# zeroport.net
KiCad netlist of a schematic drawn in EAGLE
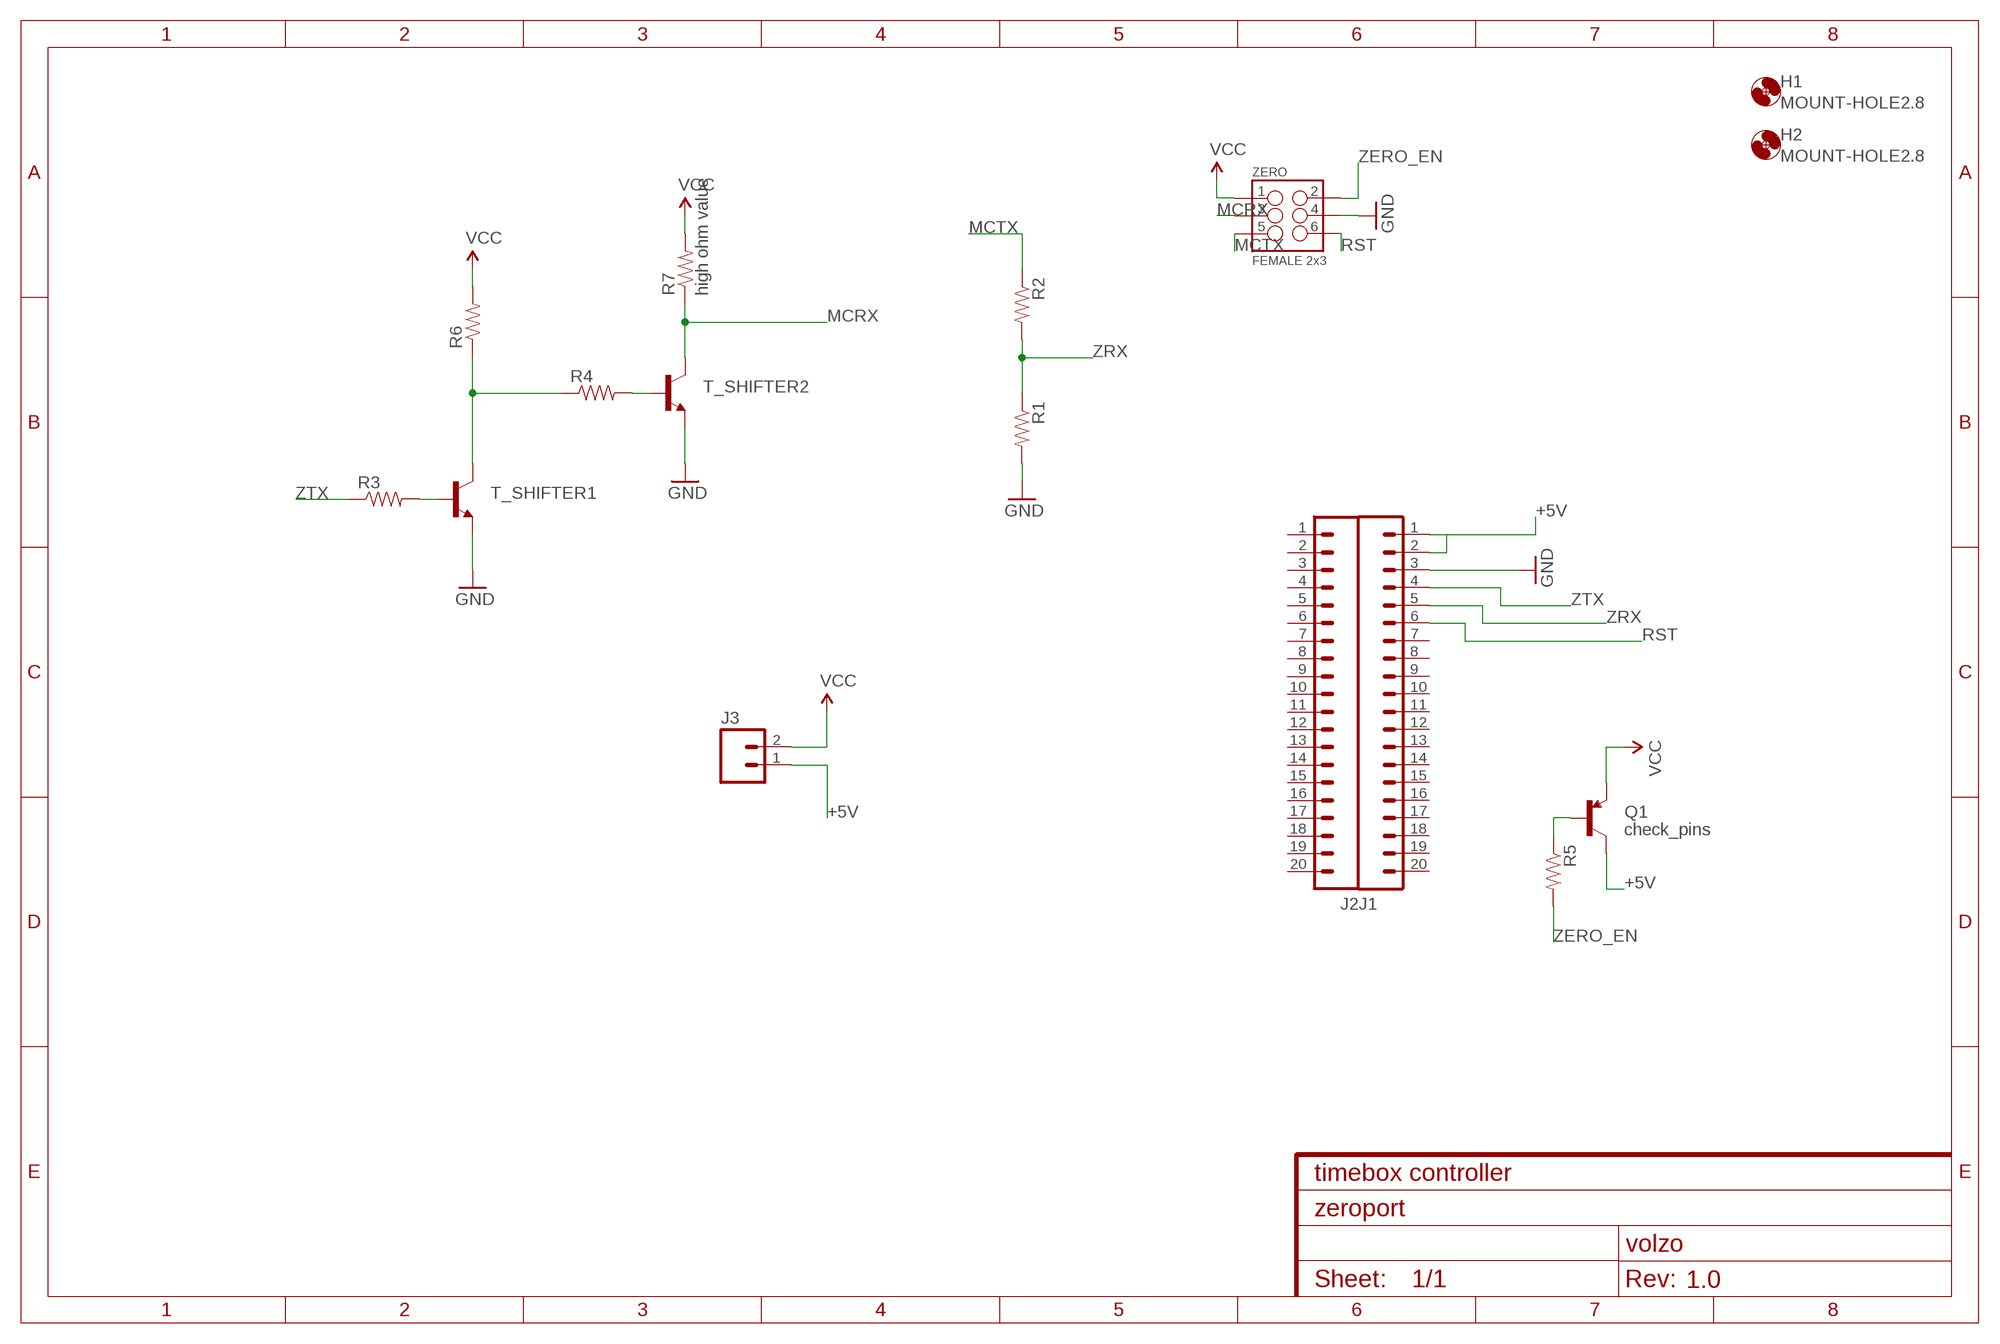
[diagram p0: schematic, sheet 1]

(export (version "E")
  (design (tool "Eeschema 10.0.6"))
  (components
    (comp (ref "H1")
      (value "MOUNT-HOLE2.8")
      (footprint "eagle-import:2,8")
      (libsource (lib "eagle-import") (part "MOUNT-HOLE2.8"))
    )
    (comp (ref "H2")
      (value "MOUNT-HOLE2.8")
      (footprint "eagle-import:2,8")
      (libsource (lib "eagle-import") (part "MOUNT-HOLE2.8"))
    )
    (comp (ref "J1")
      (value "M20LOCK")
      (footprint "eagle-import:1X20_LOCK")
      (libsource (lib "eagle-import") (part "M20LOCK"))
    )
    (comp (ref "J2")
      (value "M20LOCK")
      (footprint "eagle-import:1X20_LOCK")
      (libsource (lib "eagle-import") (part "M20LOCK"))
    )
    (comp (ref "J3")
      (value "M02LOCK")
      (footprint "eagle-import:1X02_LOCK")
      (libsource (lib "eagle-import") (part "M02LOCK"))
    )
    (comp (ref "Q1")
      (value "check_pins")
      (footprint "eagle-import:TO-92")
      (libsource (lib "eagle-import") (part "TRANSISTOR_PNPTO92"))
    )
    (comp (ref "R1")
      (value "RESISTORPTH-1/4W")
      (footprint "eagle-import:AXIAL-0.4")
      (libsource (lib "eagle-import") (part "RESISTORPTH-1/4W"))
    )
    (comp (ref "R2")
      (value "RESISTORPTH-1/4W")
      (footprint "eagle-import:AXIAL-0.4")
      (libsource (lib "eagle-import") (part "RESISTORPTH-1/4W"))
    )
    (comp (ref "R3")
      (value "RESISTORPTH-1/4W")
      (footprint "eagle-import:AXIAL-0.4")
      (libsource (lib "eagle-import") (part "RESISTORPTH-1/4W"))
    )
    (comp (ref "R4")
      (value "RESISTORPTH-1/4W")
      (footprint "eagle-import:AXIAL-0.4")
      (libsource (lib "eagle-import") (part "RESISTORPTH-1/4W"))
    )
    (comp (ref "R5")
      (value "RESISTORPTH-1/4W")
      (footprint "eagle-import:AXIAL-0.4")
      (libsource (lib "eagle-import") (part "RESISTORPTH-1/4W"))
    )
    (comp (ref "R6")
      (value "RESISTORPTH-1/4W")
      (footprint "eagle-import:AXIAL-0.4")
      (libsource (lib "eagle-import") (part "RESISTORPTH-1/4W"))
    )
    (comp (ref "R7")
      (value "high ohm value")
      (footprint "eagle-import:AXIAL-0.4")
      (libsource (lib "eagle-import") (part "RESISTORPTH-1/4W"))
    )
    (comp (ref "T_SHIFTER1")
      (value "TRANSISTOR_NPN2N3904")
      (footprint "eagle-import:TO-92")
      (libsource (lib "eagle-import") (part "TRANSISTOR_NPN2N3904"))
    )
    (comp (ref "T_SHIFTER2")
      (value "TRANSISTOR_NPN2N3904")
      (footprint "eagle-import:TO-92")
      (libsource (lib "eagle-import") (part "TRANSISTOR_NPN2N3904"))
    )
    (comp (ref "ZERO")
      (value "FEMALE 2x3")
      (footprint "eagle-import:2X3")
      (libsource (lib "eagle-import") (part "M03X2FEMALE"))
    )
  )
  (nets
    (net (code "1") (name "/+5V") (class "Default")
      (node (ref "J1") (pin "1") (pinfunction "1_1") (pintype "passive"))
      (node (ref "J3") (pin "1") (pinfunction "1_1") (pintype "passive"))
      (node (ref "Q1") (pin "3") (pinfunction "C_3") (pintype "passive"))
    )
    (net (code "2") (name "/MCRX") (class "Default")
      (node (ref "R7") (pin "P$1") (pinfunction "1_P$1") (pintype "passive"))
      (node (ref "T_SHIFTER2") (pin "3") (pinfunction "C_3") (pintype "passive"))
      (node (ref "ZERO") (pin "3") (pinfunction "3_3") (pintype "bidirectional"))
    )
    (net (code "3") (name "/MCTX") (class "Default")
      (node (ref "R2") (pin "P$1") (pinfunction "1_P$1") (pintype "passive"))
      (node (ref "ZERO") (pin "5") (pinfunction "5_5") (pintype "bidirectional"))
    )
    (net (code "4") (name "/RST") (class "Default")
      (node (ref "J1") (pin "6") (pinfunction "6_6") (pintype "passive"))
      (node (ref "ZERO") (pin "6") (pinfunction "6_6") (pintype "bidirectional"))
    )
    (net (code "5") (name "/ZERO_EN") (class "Default")
      (node (ref "R5") (pin "P$2") (pinfunction "2_P$2") (pintype "passive"))
      (node (ref "ZERO") (pin "2") (pinfunction "2_2") (pintype "bidirectional"))
    )
    (net (code "6") (name "/ZRX") (class "Default")
      (node (ref "J1") (pin "5") (pinfunction "5_5") (pintype "passive"))
      (node (ref "R1") (pin "P$1") (pinfunction "1_P$1") (pintype "passive"))
      (node (ref "R2") (pin "P$2") (pinfunction "2_P$2") (pintype "passive"))
    )
    (net (code "7") (name "/ZTX") (class "Default")
      (node (ref "J1") (pin "4") (pinfunction "4_4") (pintype "passive"))
      (node (ref "R3") (pin "P$1") (pinfunction "1_P$1") (pintype "passive"))
    )
    (net (code "8") (name "GND") (class "Default")
      (node (ref "J1") (pin "3") (pinfunction "3_3") (pintype "passive"))
      (node (ref "R1") (pin "P$2") (pinfunction "2_P$2") (pintype "passive"))
      (node (ref "T_SHIFTER1") (pin "1") (pinfunction "E_1") (pintype "passive"))
      (node (ref "T_SHIFTER2") (pin "1") (pinfunction "E_1") (pintype "passive"))
      (node (ref "ZERO") (pin "4") (pinfunction "4_4") (pintype "bidirectional"))
    )
    (net (code "9") (name "Net-(Q1-B)") (class "Default")
      (node (ref "Q1") (pin "2") (pinfunction "B_2") (pintype "passive"))
      (node (ref "R5") (pin "P$1") (pinfunction "1_P$1") (pintype "passive"))
    )
    (net (code "10") (name "Net-(R3-2)") (class "Default")
      (node (ref "R3") (pin "P$2") (pinfunction "2_P$2") (pintype "passive"))
      (node (ref "T_SHIFTER1") (pin "2") (pinfunction "B_2") (pintype "passive"))
    )
    (net (code "11") (name "Net-(R4-1)") (class "Default")
      (node (ref "R4") (pin "P$1") (pinfunction "1_P$1") (pintype "passive"))
      (node (ref "R6") (pin "P$1") (pinfunction "1_P$1") (pintype "passive"))
      (node (ref "T_SHIFTER1") (pin "3") (pinfunction "C_3") (pintype "passive"))
    )
    (net (code "12") (name "Net-(R4-2)") (class "Default")
      (node (ref "R4") (pin "P$2") (pinfunction "2_P$2") (pintype "passive"))
      (node (ref "T_SHIFTER2") (pin "2") (pinfunction "B_2") (pintype "passive"))
    )
    (net (code "13") (name "VCC") (class "Default")
      (node (ref "J3") (pin "2") (pinfunction "2_2") (pintype "passive"))
      (node (ref "Q1") (pin "1") (pinfunction "E_1") (pintype "passive"))
      (node (ref "R6") (pin "P$2") (pinfunction "2_P$2") (pintype "passive"))
      (node (ref "R7") (pin "P$2") (pinfunction "2_P$2") (pintype "passive"))
      (node (ref "ZERO") (pin "1") (pinfunction "1_1") (pintype "bidirectional"))
    )
    (net (code "14") (name "unconnected-(J1-Pad2)") (class "Default")
      (node (ref "J1") (pin "2") (pinfunction "2_2") (pintype "passive"))
    )
    (net (code "15") (name "unconnected-(J1-Pad7)") (class "Default")
      (node (ref "J1") (pin "7") (pinfunction "7_7") (pintype "passive"))
    )
    (net (code "16") (name "unconnected-(J1-Pad8)") (class "Default")
      (node (ref "J1") (pin "8") (pinfunction "8_8") (pintype "passive"))
    )
    (net (code "17") (name "unconnected-(J1-Pad9)") (class "Default")
      (node (ref "J1") (pin "9") (pinfunction "9_9") (pintype "passive"))
    )
    (net (code "18") (name "unconnected-(J1-Pad10)") (class "Default")
      (node (ref "J1") (pin "10") (pinfunction "10_10") (pintype "passive"))
    )
    (net (code "19") (name "unconnected-(J1-Pad11)") (class "Default")
      (node (ref "J1") (pin "11") (pinfunction "11_11") (pintype "passive"))
    )
    (net (code "20") (name "unconnected-(J1-Pad12)") (class "Default")
      (node (ref "J1") (pin "12") (pinfunction "12_12") (pintype "passive"))
    )
    (net (code "21") (name "unconnected-(J1-Pad13)") (class "Default")
      (node (ref "J1") (pin "13") (pinfunction "13_13") (pintype "passive"))
    )
    (net (code "22") (name "unconnected-(J1-Pad14)") (class "Default")
      (node (ref "J1") (pin "14") (pinfunction "14_14") (pintype "passive"))
    )
    (net (code "23") (name "unconnected-(J1-Pad15)") (class "Default")
      (node (ref "J1") (pin "15") (pinfunction "15_15") (pintype "passive"))
    )
    (net (code "24") (name "unconnected-(J1-Pad16)") (class "Default")
      (node (ref "J1") (pin "16") (pinfunction "16_16") (pintype "passive"))
    )
    (net (code "25") (name "unconnected-(J1-Pad17)") (class "Default")
      (node (ref "J1") (pin "17") (pinfunction "17_17") (pintype "passive"))
    )
    (net (code "26") (name "unconnected-(J1-Pad18)") (class "Default")
      (node (ref "J1") (pin "18") (pinfunction "18_18") (pintype "passive"))
    )
    (net (code "27") (name "unconnected-(J1-Pad19)") (class "Default")
      (node (ref "J1") (pin "19") (pinfunction "19_19") (pintype "passive"))
    )
    (net (code "28") (name "unconnected-(J1-Pad20)") (class "Default")
      (node (ref "J1") (pin "20") (pinfunction "20_20") (pintype "passive"))
    )
    (net (code "29") (name "unconnected-(J2-Pad1)") (class "Default")
      (node (ref "J2") (pin "1") (pinfunction "1_1") (pintype "passive"))
    )
    (net (code "30") (name "unconnected-(J2-Pad2)") (class "Default")
      (node (ref "J2") (pin "2") (pinfunction "2_2") (pintype "passive"))
    )
    (net (code "31") (name "unconnected-(J2-Pad3)") (class "Default")
      (node (ref "J2") (pin "3") (pinfunction "3_3") (pintype "passive"))
    )
    (net (code "32") (name "unconnected-(J2-Pad4)") (class "Default")
      (node (ref "J2") (pin "4") (pinfunction "4_4") (pintype "passive"))
    )
    (net (code "33") (name "unconnected-(J2-Pad5)") (class "Default")
      (node (ref "J2") (pin "5") (pinfunction "5_5") (pintype "passive"))
    )
    (net (code "34") (name "unconnected-(J2-Pad6)") (class "Default")
      (node (ref "J2") (pin "6") (pinfunction "6_6") (pintype "passive"))
    )
    (net (code "35") (name "unconnected-(J2-Pad7)") (class "Default")
      (node (ref "J2") (pin "7") (pinfunction "7_7") (pintype "passive"))
    )
    (net (code "36") (name "unconnected-(J2-Pad8)") (class "Default")
      (node (ref "J2") (pin "8") (pinfunction "8_8") (pintype "passive"))
    )
    (net (code "37") (name "unconnected-(J2-Pad9)") (class "Default")
      (node (ref "J2") (pin "9") (pinfunction "9_9") (pintype "passive"))
    )
    (net (code "38") (name "unconnected-(J2-Pad10)") (class "Default")
      (node (ref "J2") (pin "10") (pinfunction "10_10") (pintype "passive"))
    )
    (net (code "39") (name "unconnected-(J2-Pad11)") (class "Default")
      (node (ref "J2") (pin "11") (pinfunction "11_11") (pintype "passive"))
    )
    (net (code "40") (name "unconnected-(J2-Pad12)") (class "Default")
      (node (ref "J2") (pin "12") (pinfunction "12_12") (pintype "passive"))
    )
    (net (code "41") (name "unconnected-(J2-Pad13)") (class "Default")
      (node (ref "J2") (pin "13") (pinfunction "13_13") (pintype "passive"))
    )
    (net (code "42") (name "unconnected-(J2-Pad14)") (class "Default")
      (node (ref "J2") (pin "14") (pinfunction "14_14") (pintype "passive"))
    )
    (net (code "43") (name "unconnected-(J2-Pad15)") (class "Default")
      (node (ref "J2") (pin "15") (pinfunction "15_15") (pintype "passive"))
    )
    (net (code "44") (name "unconnected-(J2-Pad16)") (class "Default")
      (node (ref "J2") (pin "16") (pinfunction "16_16") (pintype "passive"))
    )
    (net (code "45") (name "unconnected-(J2-Pad17)") (class "Default")
      (node (ref "J2") (pin "17") (pinfunction "17_17") (pintype "passive"))
    )
    (net (code "46") (name "unconnected-(J2-Pad18)") (class "Default")
      (node (ref "J2") (pin "18") (pinfunction "18_18") (pintype "passive"))
    )
    (net (code "47") (name "unconnected-(J2-Pad19)") (class "Default")
      (node (ref "J2") (pin "19") (pinfunction "19_19") (pintype "passive"))
    )
    (net (code "48") (name "unconnected-(J2-Pad20)") (class "Default")
      (node (ref "J2") (pin "20") (pinfunction "20_20") (pintype "passive"))
    )
  )
)
